# GPIO.net
KiCad netlist of a schematic drawn in Altium Designer
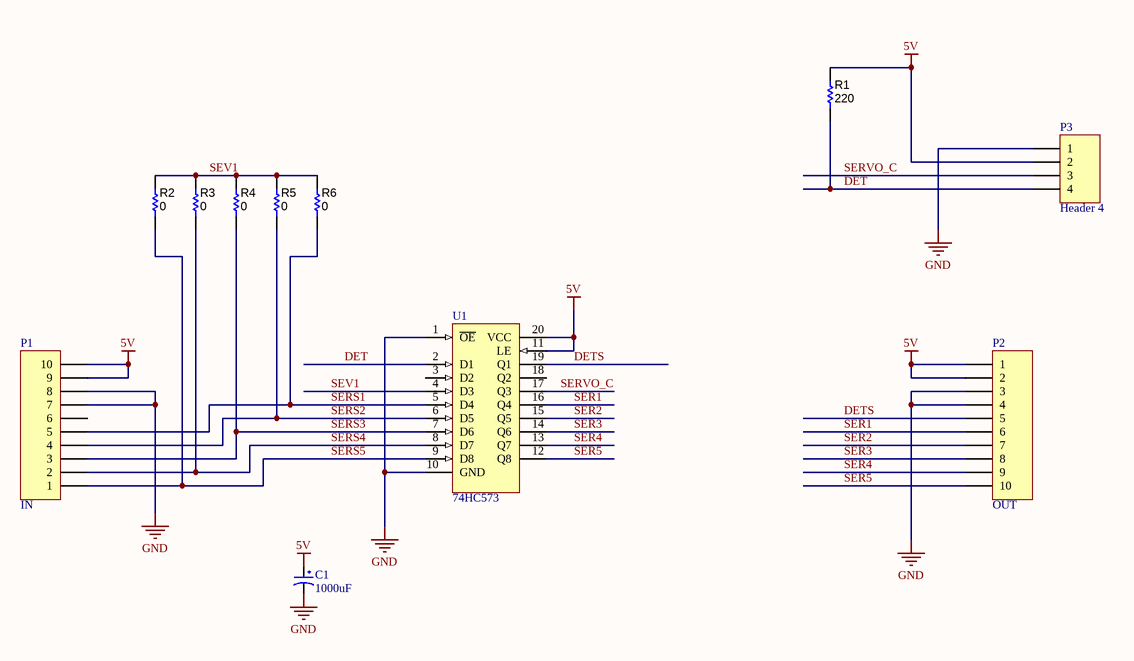
[diagram p0: GPIO.SchDoc]

(export (version "E")
  (design (tool "Eeschema 10.0.6"))
  (components
    (comp (ref "C1")
      (value "1000uF")
      (footprint "TU_NHOM_470uF_25V_MH")
      (description "TU_NHOM_1000uF_16V_MH")
      (libsource (lib "MH_DA_THU_VIEN_16122016") (part "TU_NHOM_1000uF_16V_MH"))
    )
    (comp (ref "P1")
      (value "IN")
      (footprint "JST-PH2.00-10P")
      (description "Header, 10-Pin")
      (fields (field (name "PUBLISHER") "Altium Limited"))
      (libsource (lib "") (part "Header 10_1"))
    )
    (comp (ref "P2")
      (value "OUT")
      (footprint "JST-PH2.00-10P")
      (description "Header, 10-Pin")
      (fields (field (name "PUBLISHER") "Altium Limited"))
      (libsource (lib "Miscellaneous Connectors") (part "Header 10"))
    )
    (comp (ref "P3")
      (value "Header 4")
      (footprint "SpringCON")
      (description "Header, 4-Pin")
      (fields (field (name "PUBLISHER") "Altium Limited"))
      (libsource (lib "Miscellaneous Connectors") (part "Header 4"))
    )
    (comp (ref "R1")
      (value "220")
      (footprint "Tro SMD 0805")
      (description "RES, 100, 1%, 0.1 W, 0402")
      (fields
        (field (name "PARTNUMBER") "ERJ-2RKF1000X")
        (field (name "MANUFACTURER") "Panasonic")
        (field (name "PUBLISHER") "Texas Instruments")
      )
      (libsource (lib "mySch") (part "R nho"))
    )
    (comp (ref "R2")
      (value "0")
      (footprint "Tro SMD 0805")
      (description "RES, 100, 1%, 0.1 W, 0402")
      (fields
        (field (name "PARTNUMBER") "ERJ-2RKF1000X")
        (field (name "MANUFACTURER") "Panasonic")
        (field (name "PUBLISHER") "Texas Instruments")
      )
      (libsource (lib "mySch") (part "R nho"))
    )
    (comp (ref "R3")
      (value "0")
      (footprint "Tro SMD 0805")
      (description "RES, 100, 1%, 0.1 W, 0402")
      (fields
        (field (name "PARTNUMBER") "ERJ-2RKF1000X")
        (field (name "MANUFACTURER") "Panasonic")
        (field (name "PUBLISHER") "Texas Instruments")
      )
      (libsource (lib "mySch") (part "R nho"))
    )
    (comp (ref "R4")
      (value "0")
      (footprint "Tro SMD 0805")
      (description "RES, 100, 1%, 0.1 W, 0402")
      (fields
        (field (name "PARTNUMBER") "ERJ-2RKF1000X")
        (field (name "MANUFACTURER") "Panasonic")
        (field (name "PUBLISHER") "Texas Instruments")
      )
      (libsource (lib "mySch") (part "R nho"))
    )
    (comp (ref "R5")
      (value "0")
      (footprint "Tro SMD 0805")
      (description "RES, 100, 1%, 0.1 W, 0402")
      (fields
        (field (name "PARTNUMBER") "ERJ-2RKF1000X")
        (field (name "MANUFACTURER") "Panasonic")
        (field (name "PUBLISHER") "Texas Instruments")
      )
      (libsource (lib "mySch") (part "R nho"))
    )
    (comp (ref "R6")
      (value "0")
      (footprint "Tro SMD 0805")
      (description "RES, 100, 1%, 0.1 W, 0402")
      (fields
        (field (name "PARTNUMBER") "ERJ-2RKF1000X")
        (field (name "MANUFACTURER") "Panasonic")
        (field (name "PUBLISHER") "Texas Instruments")
      )
      (libsource (lib "mySch") (part "R nho"))
    )
    (comp (ref "U1")
      (value "74HC573")
      (footprint "SOIC-20")
      (description "Octal D-Type Latch with 3-State Output Non-Inverting")
      (fields (field (name "COPYRIGHT BY") "VanDungEvn@Gmail.com"))
      (libsource (lib "MH_DA_THU_VIEN_16122016") (part "74HC573 DIP20 IC Flip-Flop_MH"))
    )
  )
  (nets
    (net (code "1") (name "/DET") (class "Default")
      (node (ref "P3") (pin "4") (pinfunction "4_4") (pintype "passive"))
      (node (ref "R1") (pin "2") (pinfunction "2_2") (pintype "passive"))
      (node (ref "U1") (pin "2") (pinfunction "D1_2") (pintype "input"))
    )
    (net (code "2") (name "/DETS") (class "Default")
      (node (ref "P2") (pin "5") (pinfunction "5_5") (pintype "passive"))
      (node (ref "U1") (pin "19") (pinfunction "Q1_19") (pintype "tri_state"))
    )
    (net (code "3") (name "/SER1") (class "Default")
      (node (ref "P2") (pin "6") (pinfunction "6_6") (pintype "passive"))
      (node (ref "U1") (pin "16") (pinfunction "Q4_16") (pintype "tri_state"))
    )
    (net (code "4") (name "/SER2") (class "Default")
      (node (ref "P2") (pin "7") (pinfunction "7_7") (pintype "passive"))
      (node (ref "U1") (pin "15") (pinfunction "Q5_15") (pintype "tri_state"))
    )
    (net (code "5") (name "/SER3") (class "Default")
      (node (ref "P2") (pin "8") (pinfunction "8_8") (pintype "passive"))
      (node (ref "U1") (pin "14") (pinfunction "Q6_14") (pintype "tri_state"))
    )
    (net (code "6") (name "/SER4") (class "Default")
      (node (ref "P2") (pin "9") (pinfunction "9_9") (pintype "passive"))
      (node (ref "U1") (pin "13") (pinfunction "Q7_13") (pintype "tri_state"))
    )
    (net (code "7") (name "/SER5") (class "Default")
      (node (ref "P2") (pin "10") (pinfunction "10_10") (pintype "passive"))
      (node (ref "U1") (pin "12") (pinfunction "Q8_12") (pintype "tri_state"))
    )
    (net (code "8") (name "/SERS1") (class "Default")
      (node (ref "P1") (pin "5") (pinfunction "5_5") (pintype "passive"))
      (node (ref "R6") (pin "2") (pinfunction "2_2") (pintype "passive"))
      (node (ref "U1") (pin "5") (pinfunction "D4_5") (pintype "input"))
    )
    (net (code "9") (name "/SERS2") (class "Default")
      (node (ref "P1") (pin "4") (pinfunction "4_4") (pintype "passive"))
      (node (ref "R5") (pin "2") (pinfunction "2_2") (pintype "passive"))
      (node (ref "U1") (pin "6") (pinfunction "D5_6") (pintype "input"))
    )
    (net (code "10") (name "/SERS3") (class "Default")
      (node (ref "P1") (pin "3") (pinfunction "3_3") (pintype "passive"))
      (node (ref "R4") (pin "2") (pinfunction "2_2") (pintype "passive"))
      (node (ref "U1") (pin "7") (pinfunction "D6_7") (pintype "input"))
    )
    (net (code "11") (name "/SERS4") (class "Default")
      (node (ref "P1") (pin "2") (pinfunction "2_2") (pintype "passive"))
      (node (ref "R3") (pin "2") (pinfunction "2_2") (pintype "passive"))
      (node (ref "U1") (pin "8") (pinfunction "D7_8") (pintype "input"))
    )
    (net (code "12") (name "/SERS5") (class "Default")
      (node (ref "P1") (pin "1") (pinfunction "1_1") (pintype "passive"))
      (node (ref "R2") (pin "2") (pinfunction "2_2") (pintype "passive"))
      (node (ref "U1") (pin "9") (pinfunction "D8_9") (pintype "input"))
    )
    (net (code "13") (name "/SERVO_C") (class "Default")
      (node (ref "P3") (pin "3") (pinfunction "3_3") (pintype "passive"))
      (node (ref "U1") (pin "17") (pinfunction "Q3_17") (pintype "tri_state"))
    )
    (net (code "14") (name "/SEV1") (class "Default")
      (node (ref "R2") (pin "1") (pinfunction "1_1") (pintype "passive"))
      (node (ref "R3") (pin "1") (pinfunction "1_1") (pintype "passive"))
      (node (ref "R4") (pin "1") (pinfunction "1_1") (pintype "passive"))
      (node (ref "R5") (pin "1") (pinfunction "1_1") (pintype "passive"))
      (node (ref "R6") (pin "1") (pinfunction "1_1") (pintype "passive"))
      (node (ref "U1") (pin "4") (pinfunction "D3_4") (pintype "input"))
    )
    (net (code "15") (name "5V") (class "Default")
      (node (ref "C1") (pin "1") (pinfunction "1_1") (pintype "passive"))
      (node (ref "P1") (pin "10") (pinfunction "10_10") (pintype "passive"))
      (node (ref "P1") (pin "9") (pinfunction "9_9") (pintype "passive"))
      (node (ref "P2") (pin "1") (pinfunction "1_1") (pintype "passive"))
      (node (ref "P2") (pin "2") (pinfunction "2_2") (pintype "passive"))
      (node (ref "P3") (pin "2") (pinfunction "2_2") (pintype "passive"))
      (node (ref "R1") (pin "1") (pinfunction "1_1") (pintype "passive"))
      (node (ref "U1") (pin "11") (pinfunction "LE_11") (pintype "input"))
      (node (ref "U1") (pin "20") (pinfunction "VCC_20") (pintype "tri_state"))
    )
    (net (code "16") (name "GND") (class "Default")
      (node (ref "C1") (pin "2") (pinfunction "2_2") (pintype "passive"))
      (node (ref "P1") (pin "7") (pinfunction "7_7") (pintype "passive"))
      (node (ref "P1") (pin "8") (pinfunction "8_8") (pintype "passive"))
      (node (ref "P2") (pin "3") (pinfunction "3_3") (pintype "passive"))
      (node (ref "P2") (pin "4") (pinfunction "4_4") (pintype "passive"))
      (node (ref "P3") (pin "1") (pinfunction "1_1") (pintype "passive"))
      (node (ref "U1") (pin "1") (pinfunction "~{OE}_1") (pintype "input"))
      (node (ref "U1") (pin "10") (pinfunction "GND_10") (pintype "tri_state"))
    )
    (net (code "17") (name "unconnected-(P1-Pad6)") (class "Default")
      (node (ref "P1") (pin "6") (pinfunction "6_6") (pintype "passive"))
    )
    (net (code "18") (name "unconnected-(U1-D2-Pad3)") (class "Default")
      (node (ref "U1") (pin "3") (pinfunction "D2_3") (pintype "input"))
    )
    (net (code "19") (name "unconnected-(U1-Q2-Pad18)") (class "Default")
      (node (ref "U1") (pin "18") (pinfunction "Q2_18") (pintype "tri_state"))
    )
  )
)
